# LCDTFT_FPC40P_LVDS_HC070IY30025.net
KiCad netlist of a schematic drawn in Altium Designer
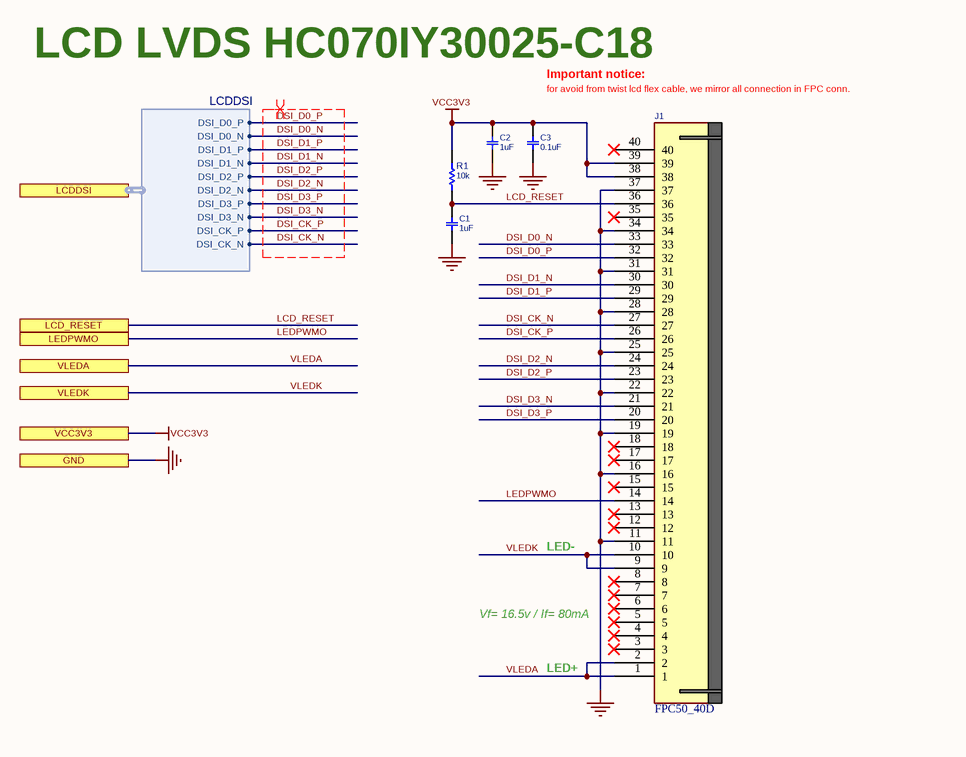
[diagram p0: LCDTFT_FPC40P_LVDS_HC070IY30025.SchDoc]

(export (version "E")
  (design (tool "Eeschema 10.0.6"))
  (components
    (comp (ref "C1")
      (value "1uF")
      (footprint "C0402")
      (description "CAP, MLCC")
      (fields (field (name "MANF_P#") "CL05A105KO5NNND") (field (name "MANF") "Samsung"))
      (libsource (lib "passive_smd") (part "CAP_SMD_MLCC"))
    )
    (comp (ref "C2")
      (value "1uF")
      (footprint "C0402")
      (description "CAP, MLCC")
      (fields (field (name "MANF_P#") "CL05A105KO5NNND") (field (name "MANF") "Samsung"))
      (libsource (lib "passive_smd") (part "CAP_SMD_MLCC"))
    )
    (comp (ref "C3")
      (value "0.1uF")
      (footprint "C0402")
      (description "CAP, MLCC")
      (fields (field (name "MANF_P#") "GRM155R71H104KE14D") (field (name "MANF") "Murata"))
      (libsource (lib "passive_smd") (part "CAP_SMD_MLCC"))
    )
    (comp (ref "J1")
      (value "FPC50_40D")
      (footprint "FPC50_40D_FFC2B29")
      (description "CONN, FPC, 0.50mm pitch, RightAngle, Dual side Contact")
      (fields (field (name "MANF") "GCT") (field (name "MANF_P#") "FFC2B29-40-G"))
      (libsource (lib "conn_fpc") (part "FPC50_40D_FFC2B29"))
    )
    (comp (ref "R1")
      (value "10k")
      (footprint "R0402")
      (description "RESISTOR, SMD")
      (libsource (lib "passive_res_smd") (part "RES_SMD"))
    )
  )
  (nets
    (net (code "2") (name "/DSI_CK_N") (class "Default")
      (node (ref "J1") (pin "27") (pinfunction "27_27") (pintype "passive"))
    )
    (net (code "3") (name "/DSI_CK_P") (class "Default")
      (node (ref "J1") (pin "26") (pinfunction "26_26") (pintype "passive"))
    )
    (net (code "4") (name "/DSI_D0_N") (class "Default")
      (node (ref "J1") (pin "33") (pinfunction "33_33") (pintype "passive"))
    )
    (net (code "5") (name "/DSI_D0_P") (class "Default")
      (node (ref "J1") (pin "32") (pinfunction "32_32") (pintype "passive"))
    )
    (net (code "6") (name "/DSI_D1_N") (class "Default")
      (node (ref "J1") (pin "30") (pinfunction "30_30") (pintype "passive"))
    )
    (net (code "7") (name "/DSI_D1_P") (class "Default")
      (node (ref "J1") (pin "29") (pinfunction "29_29") (pintype "passive"))
    )
    (net (code "8") (name "/DSI_D2_N") (class "Default")
      (node (ref "J1") (pin "24") (pinfunction "24_24") (pintype "passive"))
    )
    (net (code "9") (name "/DSI_D2_P") (class "Default")
      (node (ref "J1") (pin "23") (pinfunction "23_23") (pintype "passive"))
    )
    (net (code "10") (name "/DSI_D3_N") (class "Default")
      (node (ref "J1") (pin "21") (pinfunction "21_21") (pintype "passive"))
    )
    (net (code "11") (name "/DSI_D3_P") (class "Default")
      (node (ref "J1") (pin "20") (pinfunction "20_20") (pintype "passive"))
    )
    (net (code "12") (name "/LCD_RESET") (class "Default")
      (node (ref "C1") (pin "1") (pinfunction "1_1") (pintype "passive"))
      (node (ref "J1") (pin "36") (pinfunction "36_36") (pintype "passive"))
      (node (ref "R1") (pin "2") (pinfunction "2_2") (pintype "passive"))
    )
    (net (code "13") (name "/LEDPWMO") (class "Default")
      (node (ref "J1") (pin "14") (pinfunction "14_14") (pintype "passive"))
    )
    (net (code "14") (name "/VLEDA") (class "Default")
      (node (ref "J1") (pin "1") (pinfunction "1_1") (pintype "passive"))
      (node (ref "J1") (pin "2") (pinfunction "2_2") (pintype "passive"))
    )
    (net (code "15") (name "/VLEDK") (class "Default")
      (node (ref "J1") (pin "10") (pinfunction "10_10") (pintype "passive"))
      (node (ref "J1") (pin "9") (pinfunction "9_9") (pintype "passive"))
    )
    (net (code "17") (name "GND") (class "Default")
      (node (ref "C1") (pin "2") (pinfunction "2_2") (pintype "passive"))
      (node (ref "C2") (pin "2") (pinfunction "2_2") (pintype "passive"))
      (node (ref "C3") (pin "2") (pinfunction "2_2") (pintype "passive"))
      (node (ref "J1") (pin "11") (pinfunction "11_11") (pintype "passive"))
      (node (ref "J1") (pin "16") (pinfunction "16_16") (pintype "passive"))
      (node (ref "J1") (pin "19") (pinfunction "19_19") (pintype "passive"))
      (node (ref "J1") (pin "22") (pinfunction "22_22") (pintype "passive"))
      (node (ref "J1") (pin "25") (pinfunction "25_25") (pintype "passive"))
      (node (ref "J1") (pin "28") (pinfunction "28_28") (pintype "passive"))
      (node (ref "J1") (pin "31") (pinfunction "31_31") (pintype "passive"))
      (node (ref "J1") (pin "34") (pinfunction "34_34") (pintype "passive"))
      (node (ref "J1") (pin "37") (pinfunction "37_37") (pintype "passive"))
    )
    (net (code "18") (name "VCC3V3") (class "Default")
      (node (ref "C2") (pin "1") (pinfunction "1_1") (pintype "passive"))
      (node (ref "C3") (pin "1") (pinfunction "1_1") (pintype "passive"))
      (node (ref "J1") (pin "38") (pinfunction "38_38") (pintype "passive"))
      (node (ref "J1") (pin "39") (pinfunction "39_39") (pintype "passive"))
      (node (ref "R1") (pin "1") (pinfunction "1_1") (pintype "passive"))
    )
    (net (code "19") (name "unconnected-(J1-Pad3)") (class "Default")
      (node (ref "J1") (pin "3") (pinfunction "3_3") (pintype "passive+no_connect"))
    )
    (net (code "20") (name "unconnected-(J1-Pad4)") (class "Default")
      (node (ref "J1") (pin "4") (pinfunction "4_4") (pintype "passive+no_connect"))
    )
    (net (code "21") (name "unconnected-(J1-Pad5)") (class "Default")
      (node (ref "J1") (pin "5") (pinfunction "5_5") (pintype "passive+no_connect"))
    )
    (net (code "22") (name "unconnected-(J1-Pad6)") (class "Default")
      (node (ref "J1") (pin "6") (pinfunction "6_6") (pintype "passive+no_connect"))
    )
    (net (code "23") (name "unconnected-(J1-Pad7)") (class "Default")
      (node (ref "J1") (pin "7") (pinfunction "7_7") (pintype "passive+no_connect"))
    )
    (net (code "24") (name "unconnected-(J1-Pad8)") (class "Default")
      (node (ref "J1") (pin "8") (pinfunction "8_8") (pintype "passive+no_connect"))
    )
    (net (code "25") (name "unconnected-(J1-Pad12)") (class "Default")
      (node (ref "J1") (pin "12") (pinfunction "12_12") (pintype "passive+no_connect"))
    )
    (net (code "26") (name "unconnected-(J1-Pad13)") (class "Default")
      (node (ref "J1") (pin "13") (pinfunction "13_13") (pintype "passive+no_connect"))
    )
    (net (code "27") (name "unconnected-(J1-Pad15)") (class "Default")
      (node (ref "J1") (pin "15") (pinfunction "15_15") (pintype "passive+no_connect"))
    )
    (net (code "28") (name "unconnected-(J1-Pad17)") (class "Default")
      (node (ref "J1") (pin "17") (pinfunction "17_17") (pintype "passive+no_connect"))
    )
    (net (code "29") (name "unconnected-(J1-Pad18)") (class "Default")
      (node (ref "J1") (pin "18") (pinfunction "18_18") (pintype "passive+no_connect"))
    )
    (net (code "30") (name "unconnected-(J1-Pad35)") (class "Default")
      (node (ref "J1") (pin "35") (pinfunction "35_35") (pintype "passive+no_connect"))
    )
    (net (code "31") (name "unconnected-(J1-Pad40)") (class "Default")
      (node (ref "J1") (pin "40") (pinfunction "40_40") (pintype "passive+no_connect"))
    )
  )
)
